# On_Off.net
KiCad netlist of a schematic drawn in EAGLE
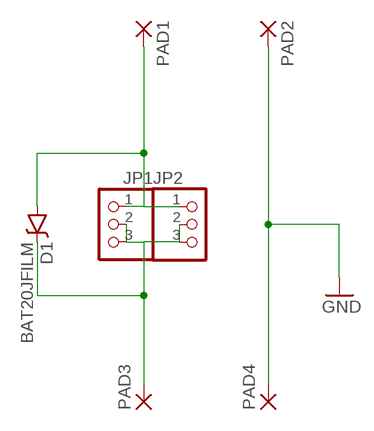
[diagram p0: schematic, sheet 1]

(export (version "E")
  (design (tool "Eeschema 10.0.6"))
  (components
    (comp (ref "D1")
      (value "BAT20JFILM")
      (footprint "eagle-import:SOD-323")
      (libsource (lib "eagle-import") (part "BAT20JFILM"))
    )
    (comp (ref "JP1")
      (value "PINHD-1X3")
      (footprint "eagle-import:1X03")
      (libsource (lib "eagle-import") (part "PINHD-1X3"))
    )
    (comp (ref "JP2")
      (value "PINHD-1X3")
      (footprint "eagle-import:1X03")
      (libsource (lib "eagle-import") (part "PINHD-1X3"))
    )
    (comp (ref "PAD1")
      (value "SMD5")
      (footprint "eagle-import:SMD2,54-5,08")
      (libsource (lib "eagle-import") (part "SMD5"))
    )
    (comp (ref "PAD2")
      (value "SMD5")
      (footprint "eagle-import:SMD2,54-5,08")
      (libsource (lib "eagle-import") (part "SMD5"))
    )
    (comp (ref "PAD3")
      (value "SMD5")
      (footprint "eagle-import:SMD2,54-5,08")
      (libsource (lib "eagle-import") (part "SMD5"))
    )
    (comp (ref "PAD4")
      (value "SMD5")
      (footprint "eagle-import:SMD2,54-5,08")
      (libsource (lib "eagle-import") (part "SMD5"))
    )
  )
  (nets
    (net (code "1") (name "GND") (class "Default")
      (node (ref "PAD2") (pin "1") (pinfunction "P_1") (pintype "passive"))
      (node (ref "PAD4") (pin "1") (pinfunction "P_1") (pintype "passive"))
    )
    (net (code "2") (name "Net-(PAD1-P)") (class "Default")
      (node (ref "D1") (pin "A") (pinfunction "A_A") (pintype "passive"))
      (node (ref "JP1") (pin "1") (pinfunction "1_1") (pintype "passive"))
      (node (ref "JP2") (pin "1") (pinfunction "1_1") (pintype "passive"))
      (node (ref "PAD1") (pin "1") (pinfunction "P_1") (pintype "passive"))
    )
    (net (code "3") (name "Net-(PAD3-P)") (class "Default")
      (node (ref "D1") (pin "C") (pinfunction "C_C") (pintype "passive"))
      (node (ref "JP1") (pin "2") (pinfunction "2_2") (pintype "passive"))
      (node (ref "JP1") (pin "3") (pinfunction "3_3") (pintype "passive"))
      (node (ref "JP2") (pin "2") (pinfunction "2_2") (pintype "passive"))
      (node (ref "JP2") (pin "3") (pinfunction "3_3") (pintype "passive"))
      (node (ref "PAD3") (pin "1") (pinfunction "P_1") (pintype "passive"))
    )
  )
)
